# Sno_Shoe.net
KiCad netlist of a schematic drawn in EAGLE
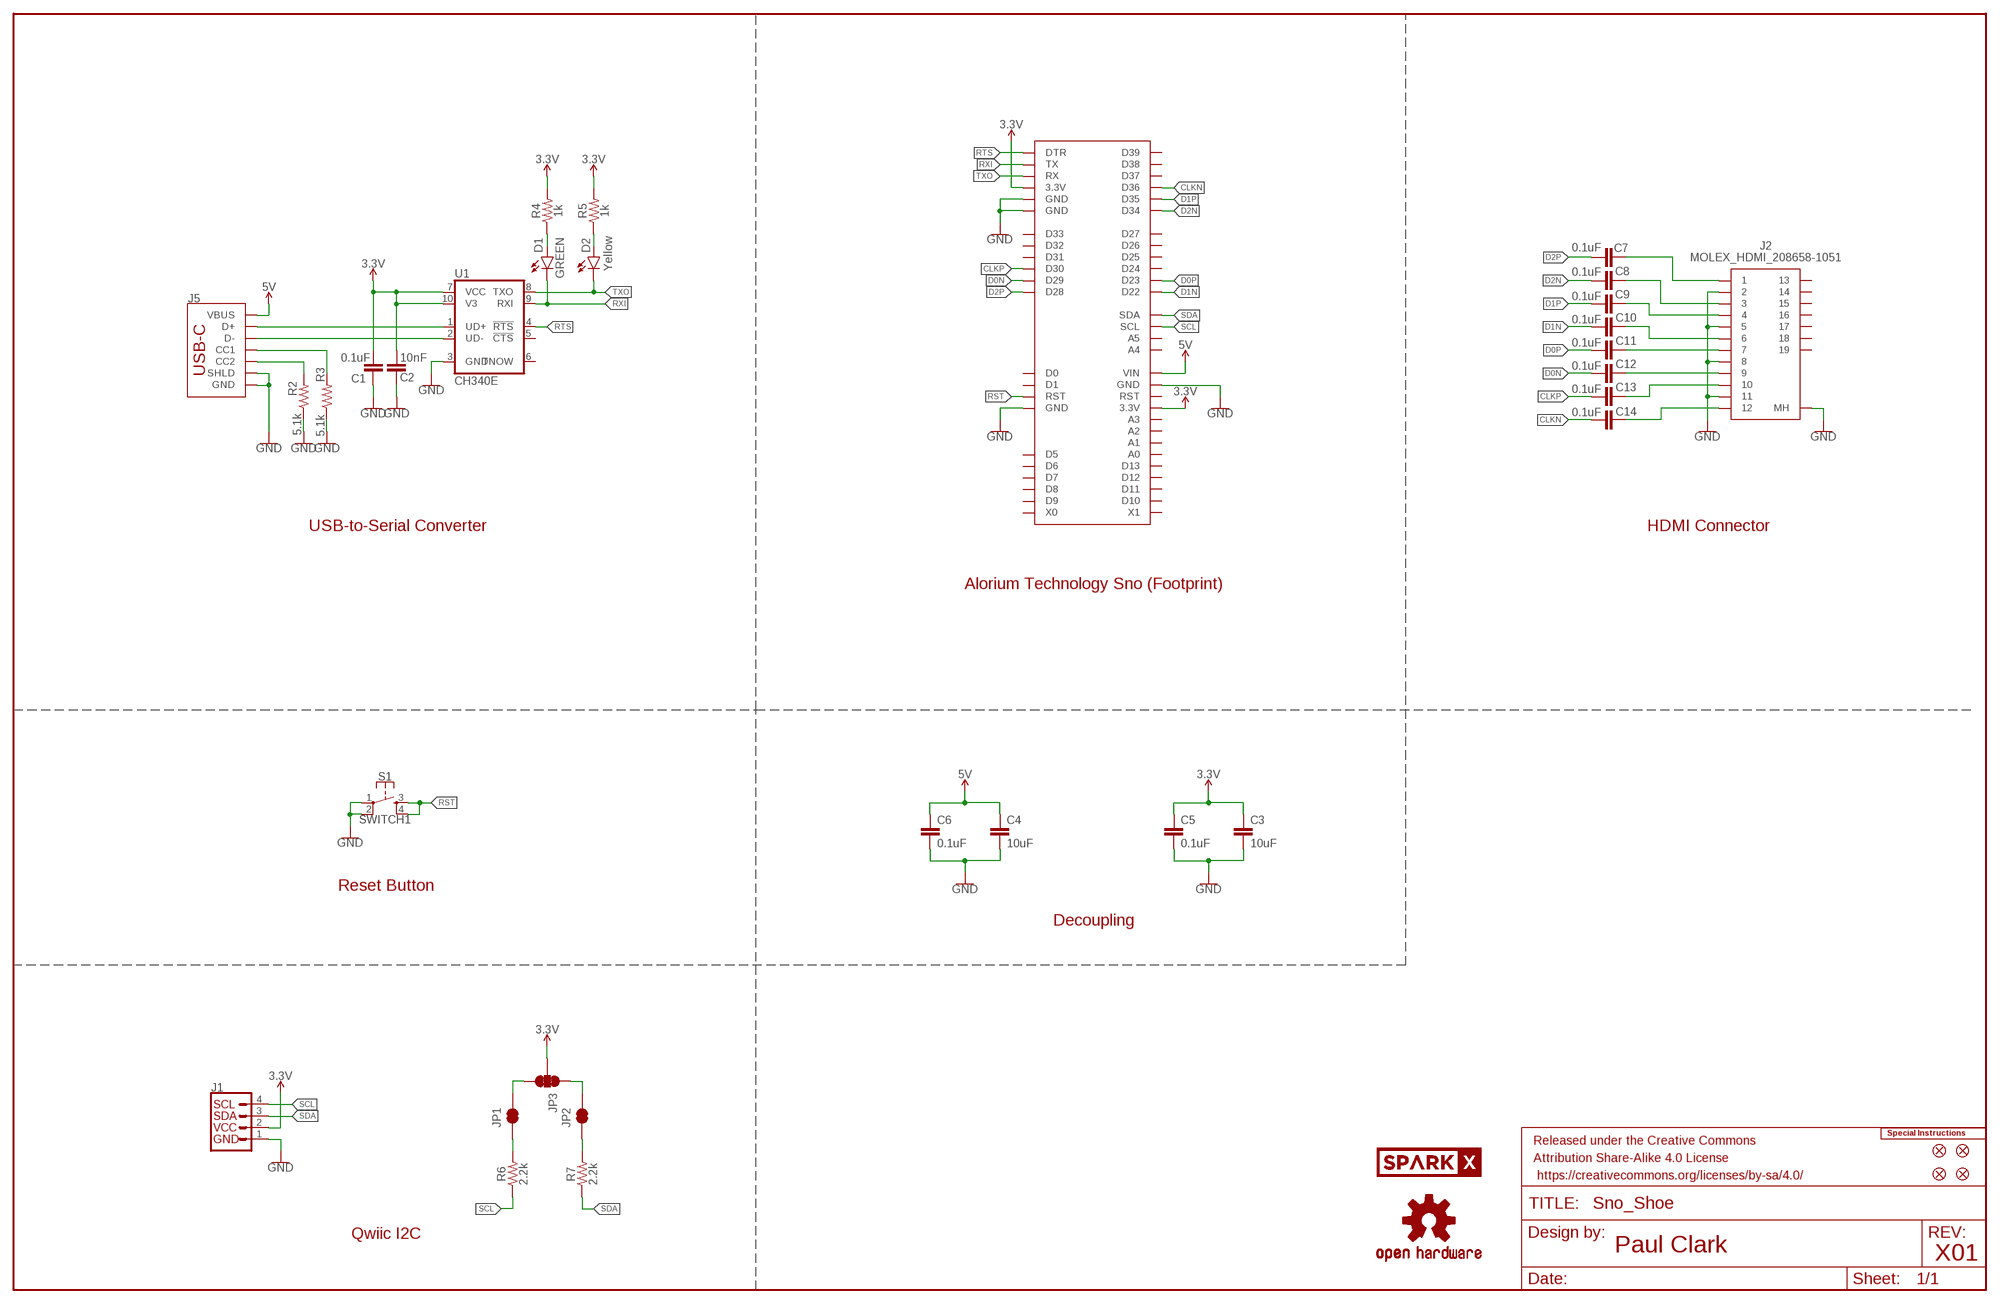
[diagram p0: schematic, sheet 1]

(export (version "E")
  (design (tool "Eeschema 10.0.6"))
  (components
    (comp (ref "C1")
      (value "0.1uF")
      (footprint "eagle-import:0402-TIGHT")
      (libsource (lib "eagle-import") (part "0.1UF-0402T-16V-10%"))
    )
    (comp (ref "C2")
      (value "10nF")
      (footprint "eagle-import:0402-TIGHT")
      (libsource (lib "eagle-import") (part "10NF-0402T-25V-10%"))
    )
    (comp (ref "C3")
      (value "10uF")
      (footprint "eagle-import:0402-TIGHT")
      (libsource (lib "eagle-import") (part "10UF-0402T-6.3V-20%"))
    )
    (comp (ref "C4")
      (value "10uF")
      (footprint "eagle-import:0805")
      (libsource (lib "eagle-import") (part "10UF-0805-10V-10%"))
    )
    (comp (ref "C5")
      (value "0.1uF")
      (footprint "eagle-import:0402-TIGHT")
      (libsource (lib "eagle-import") (part "0.1UF-0402T-10V-10%-X7R"))
    )
    (comp (ref "C6")
      (value "0.1uF")
      (footprint "eagle-import:0402-TIGHT")
      (libsource (lib "eagle-import") (part "0.1UF-0402T-10V-10%-X7R"))
    )
    (comp (ref "C7")
      (value "0.1uF")
      (footprint "eagle-import:0402-TIGHT")
      (libsource (lib "eagle-import") (part "0.1UF-0402T-10V-10%-X7R"))
    )
    (comp (ref "C8")
      (value "0.1uF")
      (footprint "eagle-import:0402-TIGHT")
      (libsource (lib "eagle-import") (part "0.1UF-0402T-10V-10%-X7R"))
    )
    (comp (ref "C9")
      (value "0.1uF")
      (footprint "eagle-import:0402-TIGHT")
      (libsource (lib "eagle-import") (part "0.1UF-0402T-10V-10%-X7R"))
    )
    (comp (ref "C10")
      (value "0.1uF")
      (footprint "eagle-import:0402-TIGHT")
      (libsource (lib "eagle-import") (part "0.1UF-0402T-10V-10%-X7R"))
    )
    (comp (ref "C11")
      (value "0.1uF")
      (footprint "eagle-import:0402-TIGHT")
      (libsource (lib "eagle-import") (part "0.1UF-0402T-10V-10%-X7R"))
    )
    (comp (ref "C12")
      (value "0.1uF")
      (footprint "eagle-import:0402-TIGHT")
      (libsource (lib "eagle-import") (part "0.1UF-0402T-10V-10%-X7R"))
    )
    (comp (ref "C13")
      (value "0.1uF")
      (footprint "eagle-import:0402-TIGHT")
      (libsource (lib "eagle-import") (part "0.1UF-0402T-10V-10%-X7R"))
    )
    (comp (ref "C14")
      (value "0.1uF")
      (footprint "eagle-import:0402-TIGHT")
      (libsource (lib "eagle-import") (part "0.1UF-0402T-10V-10%-X7R"))
    )
    (comp (ref "D1")
      (value "GREEN")
      (footprint "eagle-import:LED-0603")
      (libsource (lib "eagle-import") (part "LED-GREEN0603"))
    )
    (comp (ref "D2")
      (value "Yellow")
      (footprint "eagle-import:LED-0603")
      (libsource (lib "eagle-import") (part "LED-YELLOW0603"))
    )
    (comp (ref "FD1")
      (value "FIDUCIAL1X2")
      (footprint "eagle-import:FIDUCIAL-1X2")
      (libsource (lib "eagle-import") (part "FIDUCIAL1X2"))
    )
    (comp (ref "FD2")
      (value "FIDUCIAL1X2")
      (footprint "eagle-import:FIDUCIAL-1X2")
      (libsource (lib "eagle-import") (part "FIDUCIAL1X2"))
    )
    (comp (ref "FD3")
      (value "FIDUCIAL1X2")
      (footprint "eagle-import:FIDUCIAL-1X2")
      (libsource (lib "eagle-import") (part "FIDUCIAL1X2"))
    )
    (comp (ref "FD4")
      (value "FIDUCIAL1X2")
      (footprint "eagle-import:FIDUCIAL-1X2")
      (libsource (lib "eagle-import") (part "FIDUCIAL1X2"))
    )
    (comp (ref "FRAME1")
      (value "FRAME-LEDGER")
      (footprint "eagle-import:CREATIVE_COMMONS")
      (libsource (lib "eagle-import") (part "FRAME-LEDGER"))
    )
    (comp (ref "J1")
      (value "QWIIC_RIGHT_ANGLE")
      (footprint "eagle-import:JST04_1MM_RA")
      (libsource (lib "eagle-import") (part "QWIIC_CONNECTORJS-1MM"))
    )
    (comp (ref "J2")
      (value "MOLEX_HDMI_208658-1051")
      (footprint "eagle-import:MOLEX_HDMI_208658-1051")
      (fields
        (field (name "MANUFACTURER_PART_NUMBER") "208658-1051")
        (field (name "MOUSER_PART_NUMBER") "538-208658-1051")
      )
      (libsource (lib "eagle-import") (part "MOLEX_HDMI_208658-1051"))
    )
    (comp (ref "J5")
      (value "USB_C_4-LAYER_PADS")
      (footprint "eagle-import:USB-C-16P_4LAYER-PADS")
      (libsource (lib "eagle-import") (part "USB_C_4-LAYER_PADS"))
    )
    (comp (ref "JP1")
      (value "JUMPER-SMT_2_NC_TRACE_SILK")
      (footprint "eagle-import:SMT-JUMPER_2_NC_TRACE_SILK")
      (libsource (lib "eagle-import") (part "JUMPER-SMT_2_NC_TRACE_SILK"))
    )
    (comp (ref "JP2")
      (value "JUMPER-SMT_2_NC_TRACE_SILK")
      (footprint "eagle-import:SMT-JUMPER_2_NC_TRACE_SILK")
      (libsource (lib "eagle-import") (part "JUMPER-SMT_2_NC_TRACE_SILK"))
    )
    (comp (ref "JP3")
      (value "JUMPER-SMT_3_2-NC_TRACE_SILK")
      (footprint "eagle-import:SMT-JUMPER_3_2-NC_TRACE_SILK")
      (libsource (lib "eagle-import") (part "JUMPER-SMT_3_2-NC_TRACE_SILK"))
    )
    (comp (ref "LOGO1")
      (value "SPECIAL_INSTRUCTIONS-ORDERING")
      (footprint "eagle-import:ORDERING_INSTRUCTIONS")
      (libsource (lib "eagle-import") (part "SPECIAL_INSTRUCTIONS-ORDERING"))
    )
    (comp (ref "LOGO2")
      (value "OSHW-LOGOMINI")
      (footprint "eagle-import:OSHW-LOGO-MINI")
      (libsource (lib "eagle-import") (part "OSHW-LOGOMINI"))
    )
    (comp (ref "R2")
      (value "5.1k")
      (footprint "eagle-import:0402-TIGHT")
      (libsource (lib "eagle-import") (part "5.1KOHM-0402T-1/16W-1%"))
    )
    (comp (ref "R3")
      (value "5.1k")
      (footprint "eagle-import:0402-TIGHT")
      (libsource (lib "eagle-import") (part "5.1KOHM-0402T-1/16W-1%"))
    )
    (comp (ref "R4")
      (value "1k")
      (footprint "eagle-import:0402-TIGHT")
      (libsource (lib "eagle-import") (part "1KOHM-0402T-1/16W-1%"))
    )
    (comp (ref "R5")
      (value "1k")
      (footprint "eagle-import:0402-TIGHT")
      (libsource (lib "eagle-import") (part "1KOHM-0402T-1/16W-1%"))
    )
    (comp (ref "R6")
      (value "2.2k")
      (footprint "eagle-import:0402-TIGHT")
      (libsource (lib "eagle-import") (part "2.2KOHM-0402T-1/16W-1%"))
    )
    (comp (ref "R7")
      (value "2.2k")
      (footprint "eagle-import:0402-TIGHT")
      (libsource (lib "eagle-import") (part "2.2KOHM-0402T-1/16W-1%"))
    )
    (comp (ref "S1")
      (value "SWITCH1")
      (footprint "eagle-import:TACTILE_SWITCH_SMD_5.2MM")
      (libsource (lib "eagle-import") (part "MOMENTARY-SWITCH-SPST-2-SMD-5.2MM-TALL"))
    )
    (comp (ref "SPARKX2")
      (value "SPARKX-LOGO4")
      (footprint "eagle-import:SPARKX-MEDIUM")
      (libsource (lib "eagle-import") (part "SPARKX-LOGO4"))
    )
    (comp (ref "U$1")
      (value "SNO_MISSING_PINS")
      (footprint "eagle-import:SNO_MISSING_PINS")
      (libsource (lib "eagle-import") (part "SNO_MISSING_PINS"))
    )
    (comp (ref "U1")
      (value "CH340E")
      (footprint "eagle-import:MSOP10")
      (libsource (lib "eagle-import") (part "CH340E_MSOP10"))
    )
  )
  (nets
    (net (code "1") (name "3.3V") (class "Default")
      (node (ref "C1") (pin "1") (pinfunction "1_1") (pintype "passive"))
      (node (ref "C2") (pin "1") (pinfunction "1_1") (pintype "passive"))
      (node (ref "C3") (pin "1") (pinfunction "1_1") (pintype "passive"))
      (node (ref "C5") (pin "1") (pinfunction "1_1") (pintype "passive"))
      (node (ref "J1") (pin "2") (pinfunction "2_2") (pintype "power_in"))
      (node (ref "JP3") (pin "2") (pinfunction "2_2") (pintype "passive"))
      (node (ref "R4") (pin "2") (pinfunction "2_2") (pintype "passive"))
      (node (ref "R5") (pin "2") (pinfunction "2_2") (pintype "passive"))
      (node (ref "U$1") (pin "P$28") (pinfunction "3.3V_P$28") (pintype "bidirectional"))
      (node (ref "U$1") (pin "P$56") (pinfunction "3.3V_P$56") (pintype "power_in"))
      (node (ref "U1") (pin "10") (pinfunction "V3_10") (pintype "bidirectional"))
      (node (ref "U1") (pin "7") (pinfunction "VCC_7") (pintype "bidirectional"))
    )
    (net (code "2") (name "5V") (class "Default")
      (node (ref "C4") (pin "1") (pinfunction "1_1") (pintype "passive"))
      (node (ref "C6") (pin "1") (pinfunction "1_1") (pintype "passive"))
      (node (ref "J5") (pin "VBUS1") (pinfunction "VBUS_VBUS1") (pintype "bidirectional"))
      (node (ref "J5") (pin "VBUS2") (pinfunction "VBUS_VBUS2") (pintype "bidirectional"))
      (node (ref "U$1") (pin "P$31") (pinfunction "VIN_P$31") (pintype "power_in"))
    )
    (net (code "3") (name "CLKN") (class "Default")
      (node (ref "C14") (pin "1") (pinfunction "1_1") (pintype "passive"))
      (node (ref "U$1") (pin "P$50") (pinfunction "D36_P$50") (pintype "bidirectional"))
    )
    (net (code "4") (name "CLKP") (class "Default")
      (node (ref "C13") (pin "1") (pinfunction "1_1") (pintype "passive"))
      (node (ref "U$1") (pin "P$44") (pinfunction "D30_P$44") (pintype "bidirectional"))
    )
    (net (code "5") (name "D0N") (class "Default")
      (node (ref "C12") (pin "1") (pinfunction "1_1") (pintype "passive"))
      (node (ref "U$1") (pin "P$43") (pinfunction "D29_P$43") (pintype "bidirectional"))
    )
    (net (code "6") (name "D0P") (class "Default")
      (node (ref "C11") (pin "1") (pinfunction "1_1") (pintype "passive"))
      (node (ref "U$1") (pin "P$37") (pinfunction "D23_P$37") (pintype "bidirectional"))
    )
    (net (code "7") (name "D1N") (class "Default")
      (node (ref "C10") (pin "1") (pinfunction "1_1") (pintype "passive"))
      (node (ref "U$1") (pin "P$36") (pinfunction "D22_P$36") (pintype "bidirectional"))
    )
    (net (code "8") (name "D1P") (class "Default")
      (node (ref "C9") (pin "1") (pinfunction "1_1") (pintype "passive"))
      (node (ref "U$1") (pin "P$49") (pinfunction "D35_P$49") (pintype "bidirectional"))
    )
    (net (code "9") (name "D2N") (class "Default")
      (node (ref "C8") (pin "1") (pinfunction "1_1") (pintype "passive"))
      (node (ref "U$1") (pin "P$48") (pinfunction "D34_P$48") (pintype "bidirectional"))
    )
    (net (code "10") (name "D2P") (class "Default")
      (node (ref "C7") (pin "1") (pinfunction "1_1") (pintype "passive"))
      (node (ref "U$1") (pin "P$42") (pinfunction "D28_P$42") (pintype "bidirectional"))
    )
    (net (code "11") (name "GND") (class "Default")
      (node (ref "C1") (pin "2") (pinfunction "2_2") (pintype "passive"))
      (node (ref "C2") (pin "2") (pinfunction "2_2") (pintype "passive"))
      (node (ref "C3") (pin "2") (pinfunction "2_2") (pintype "passive"))
      (node (ref "C4") (pin "2") (pinfunction "2_2") (pintype "passive"))
      (node (ref "C5") (pin "2") (pinfunction "2_2") (pintype "passive"))
      (node (ref "C6") (pin "2") (pinfunction "2_2") (pintype "passive"))
      (node (ref "J1") (pin "1") (pinfunction "1_1") (pintype "power_in"))
      (node (ref "J2") (pin "11") (pinfunction "11_11") (pintype "bidirectional"))
      (node (ref "J2") (pin "2") (pinfunction "2_2") (pintype "bidirectional"))
      (node (ref "J2") (pin "5") (pinfunction "5_5") (pintype "bidirectional"))
      (node (ref "J2") (pin "8") (pinfunction "8_8") (pintype "bidirectional"))
      (node (ref "J2") (pin "MH1") (pinfunction "MH_MH1") (pintype "bidirectional"))
      (node (ref "J2") (pin "MH2") (pinfunction "MH_MH2") (pintype "bidirectional"))
      (node (ref "J2") (pin "MH3") (pinfunction "MH_MH3") (pintype "bidirectional"))
      (node (ref "J2") (pin "MH4") (pinfunction "MH_MH4") (pintype "bidirectional"))
      (node (ref "J5") (pin "GND") (pinfunction "GND_GND") (pintype "bidirectional"))
      (node (ref "J5") (pin "GND2") (pinfunction "GND_GND2") (pintype "bidirectional"))
      (node (ref "J5") (pin "SHLD1") (pinfunction "SHLD_SHLD1") (pintype "bidirectional"))
      (node (ref "J5") (pin "SHLD2") (pinfunction "SHLD_SHLD2") (pintype "bidirectional"))
      (node (ref "J5") (pin "SHLD3") (pinfunction "SHLD_SHLD3") (pintype "bidirectional"))
      (node (ref "J5") (pin "SHLD4") (pinfunction "SHLD_SHLD4") (pintype "bidirectional"))
      (node (ref "R2") (pin "1") (pinfunction "1_1") (pintype "passive"))
      (node (ref "R3") (pin "1") (pinfunction "1_1") (pintype "passive"))
      (node (ref "S1") (pin "1") (pinfunction "1_1") (pintype "passive"))
      (node (ref "S1") (pin "2") (pinfunction "2_2") (pintype "passive"))
      (node (ref "U$1") (pin "P$30") (pinfunction "GND_P$30") (pintype "power_in"))
      (node (ref "U$1") (pin "P$4") (pinfunction "GND_P$4") (pintype "bidirectional"))
      (node (ref "U$1") (pin "P$54") (pinfunction "GND_P$54") (pintype "power_in"))
      (node (ref "U$1") (pin "P$55") (pinfunction "GND_P$55") (pintype "power_in"))
      (node (ref "U1") (pin "3") (pinfunction "GND_3") (pintype "bidirectional"))
    )
    (net (code "12") (name "Net-(C7-Pad2)") (class "Default")
      (node (ref "C7") (pin "2") (pinfunction "2_2") (pintype "passive"))
      (node (ref "J2") (pin "1") (pinfunction "1_1") (pintype "bidirectional"))
    )
    (net (code "13") (name "Net-(C8-Pad2)") (class "Default")
      (node (ref "C8") (pin "2") (pinfunction "2_2") (pintype "passive"))
      (node (ref "J2") (pin "3") (pinfunction "3_3") (pintype "bidirectional"))
    )
    (net (code "14") (name "Net-(C9-Pad2)") (class "Default")
      (node (ref "C9") (pin "2") (pinfunction "2_2") (pintype "passive"))
      (node (ref "J2") (pin "4") (pinfunction "4_4") (pintype "bidirectional"))
    )
    (net (code "15") (name "Net-(C10-Pad2)") (class "Default")
      (node (ref "C10") (pin "2") (pinfunction "2_2") (pintype "passive"))
      (node (ref "J2") (pin "6") (pinfunction "6_6") (pintype "bidirectional"))
    )
    (net (code "16") (name "Net-(C11-Pad2)") (class "Default")
      (node (ref "C11") (pin "2") (pinfunction "2_2") (pintype "passive"))
      (node (ref "J2") (pin "7") (pinfunction "7_7") (pintype "bidirectional"))
    )
    (net (code "17") (name "Net-(C12-Pad2)") (class "Default")
      (node (ref "C12") (pin "2") (pinfunction "2_2") (pintype "passive"))
      (node (ref "J2") (pin "9") (pinfunction "9_9") (pintype "bidirectional"))
    )
    (net (code "18") (name "Net-(C13-Pad2)") (class "Default")
      (node (ref "C13") (pin "2") (pinfunction "2_2") (pintype "passive"))
      (node (ref "J2") (pin "10") (pinfunction "10_10") (pintype "bidirectional"))
    )
    (net (code "19") (name "Net-(C14-Pad2)") (class "Default")
      (node (ref "C14") (pin "2") (pinfunction "2_2") (pintype "passive"))
      (node (ref "J2") (pin "12") (pinfunction "12_12") (pintype "bidirectional"))
    )
    (net (code "20") (name "Net-(D1-PadA)") (class "Default")
      (node (ref "D1") (pin "A") (pinfunction "A_A") (pintype "passive"))
      (node (ref "R4") (pin "1") (pinfunction "1_1") (pintype "passive"))
    )
    (net (code "21") (name "Net-(D2-PadA)") (class "Default")
      (node (ref "D2") (pin "A") (pinfunction "A_A") (pintype "passive"))
      (node (ref "R5") (pin "1") (pinfunction "1_1") (pintype "passive"))
    )
    (net (code "22") (name "Net-(J5-CC1)") (class "Default")
      (node (ref "J5") (pin "A5") (pinfunction "CC1_A5") (pintype "bidirectional"))
      (node (ref "R3") (pin "2") (pinfunction "2_2") (pintype "passive"))
    )
    (net (code "23") (name "Net-(J5-CC2)") (class "Default")
      (node (ref "J5") (pin "B5") (pinfunction "CC2_B5") (pintype "bidirectional"))
      (node (ref "R2") (pin "2") (pinfunction "2_2") (pintype "passive"))
    )
    (net (code "24") (name "Net-(JP1-Pad1)") (class "Default")
      (node (ref "JP1") (pin "1") (pinfunction "1_1") (pintype "passive"))
      (node (ref "R6") (pin "2") (pinfunction "2_2") (pintype "passive"))
    )
    (net (code "25") (name "Net-(JP1-Pad2)") (class "Default")
      (node (ref "JP1") (pin "2") (pinfunction "2_2") (pintype "passive"))
      (node (ref "JP3") (pin "3") (pinfunction "3_3") (pintype "passive"))
    )
    (net (code "26") (name "Net-(JP2-Pad1)") (class "Default")
      (node (ref "JP2") (pin "1") (pinfunction "1_1") (pintype "passive"))
      (node (ref "R7") (pin "2") (pinfunction "2_2") (pintype "passive"))
    )
    (net (code "27") (name "Net-(JP2-Pad2)") (class "Default")
      (node (ref "JP2") (pin "2") (pinfunction "2_2") (pintype "passive"))
      (node (ref "JP3") (pin "1") (pinfunction "1_1") (pintype "passive"))
    )
    (net (code "28") (name "Net-(U1-UD+)") (class "Default")
      (node (ref "J5") (pin "A6") (pinfunction "D+_A6") (pintype "bidirectional"))
      (node (ref "J5") (pin "B6") (pinfunction "D+_B6") (pintype "bidirectional"))
      (node (ref "U1") (pin "1") (pinfunction "UD+_1") (pintype "bidirectional"))
    )
    (net (code "29") (name "Net-(U1-UD-)") (class "Default")
      (node (ref "J5") (pin "A7") (pinfunction "D-_A7") (pintype "bidirectional"))
      (node (ref "J5") (pin "B7") (pinfunction "D-_B7") (pintype "bidirectional"))
      (node (ref "U1") (pin "2") (pinfunction "UD-_2") (pintype "bidirectional"))
    )
    (net (code "30") (name "RST") (class "Default")
      (node (ref "S1") (pin "3") (pinfunction "3_3") (pintype "passive"))
      (node (ref "S1") (pin "4") (pinfunction "4_4") (pintype "passive"))
      (node (ref "U$1") (pin "P$3") (pinfunction "RST_P$3") (pintype "input"))
    )
    (net (code "31") (name "RTS") (class "Default")
      (node (ref "U$1") (pin "P$59") (pinfunction "DTR_P$59") (pintype "bidirectional"))
      (node (ref "U1") (pin "4") (pinfunction "~{RTS}_4") (pintype "bidirectional"))
    )
    (net (code "32") (name "RXI") (class "Default")
      (node (ref "D1") (pin "C") (pinfunction "C_C") (pintype "passive"))
      (node (ref "U$1") (pin "P$58") (pinfunction "TX_P$58") (pintype "bidirectional"))
      (node (ref "U1") (pin "9") (pinfunction "RXI_9") (pintype "bidirectional"))
    )
    (net (code "33") (name "SCL") (class "Default")
      (node (ref "J1") (pin "4") (pinfunction "4_4") (pintype "passive"))
      (node (ref "R6") (pin "1") (pinfunction "1_1") (pintype "passive"))
      (node (ref "U$1") (pin "P$34") (pinfunction "SCL_P$34") (pintype "bidirectional"))
    )
    (net (code "34") (name "SDA") (class "Default")
      (node (ref "J1") (pin "3") (pinfunction "3_3") (pintype "passive"))
      (node (ref "R7") (pin "1") (pinfunction "1_1") (pintype "passive"))
      (node (ref "U$1") (pin "P$35") (pinfunction "SDA_P$35") (pintype "bidirectional"))
    )
    (net (code "35") (name "TXO") (class "Default")
      (node (ref "D2") (pin "C") (pinfunction "C_C") (pintype "passive"))
      (node (ref "U$1") (pin "P$57") (pinfunction "RX_P$57") (pintype "bidirectional"))
      (node (ref "U1") (pin "8") (pinfunction "TXO_8") (pintype "bidirectional"))
    )
    (net (code "36") (name "unconnected-(J2-Pad13)") (class "Default")
      (node (ref "J2") (pin "13") (pinfunction "13_13") (pintype "bidirectional"))
    )
    (net (code "37") (name "unconnected-(J2-Pad14)") (class "Default")
      (node (ref "J2") (pin "14") (pinfunction "14_14") (pintype "bidirectional"))
    )
    (net (code "38") (name "unconnected-(J2-Pad15)") (class "Default")
      (node (ref "J2") (pin "15") (pinfunction "15_15") (pintype "bidirectional"))
    )
    (net (code "39") (name "unconnected-(J2-Pad16)") (class "Default")
      (node (ref "J2") (pin "16") (pinfunction "16_16") (pintype "bidirectional"))
    )
    (net (code "40") (name "unconnected-(J2-Pad17)") (class "Default")
      (node (ref "J2") (pin "17") (pinfunction "17_17") (pintype "bidirectional"))
    )
    (net (code "41") (name "unconnected-(J2-Pad18)") (class "Default")
      (node (ref "J2") (pin "18") (pinfunction "18_18") (pintype "bidirectional"))
    )
    (net (code "42") (name "unconnected-(J2-Pad19)") (class "Default")
      (node (ref "J2") (pin "19") (pinfunction "19_19") (pintype "bidirectional"))
    )
    (net (code "43") (name "unconnected-(U$1-A0-PadP$24)") (class "Default")
      (node (ref "U$1") (pin "P$24") (pinfunction "A0_P$24") (pintype "bidirectional"))
    )
    (net (code "44") (name "unconnected-(U$1-A1-PadP$25)") (class "Default")
      (node (ref "U$1") (pin "P$25") (pinfunction "A1_P$25") (pintype "bidirectional"))
    )
    (net (code "45") (name "unconnected-(U$1-A2-PadP$26)") (class "Default")
      (node (ref "U$1") (pin "P$26") (pinfunction "A2_P$26") (pintype "bidirectional"))
    )
    (net (code "46") (name "unconnected-(U$1-A3-PadP$27)") (class "Default")
      (node (ref "U$1") (pin "P$27") (pinfunction "A3_P$27") (pintype "bidirectional"))
    )
    (net (code "47") (name "unconnected-(U$1-A4-PadP$32)") (class "Default")
      (node (ref "U$1") (pin "P$32") (pinfunction "A4_P$32") (pintype "bidirectional"))
    )
    (net (code "48") (name "unconnected-(U$1-A5-PadP$33)") (class "Default")
      (node (ref "U$1") (pin "P$33") (pinfunction "A5_P$33") (pintype "bidirectional"))
    )
    (net (code "49") (name "unconnected-(U$1-D0-PadP$1)") (class "Default")
      (node (ref "U$1") (pin "P$1") (pinfunction "D0_P$1") (pintype "bidirectional"))
    )
    (net (code "50") (name "unconnected-(U$1-D1-PadP$2)") (class "Default")
      (node (ref "U$1") (pin "P$2") (pinfunction "D1_P$2") (pintype "bidirectional"))
    )
    (net (code "51") (name "unconnected-(U$1-D5-PadP$8)") (class "Default")
      (node (ref "U$1") (pin "P$8") (pinfunction "D5_P$8") (pintype "bidirectional"))
    )
    (net (code "52") (name "unconnected-(U$1-D6-PadP$9)") (class "Default")
      (node (ref "U$1") (pin "P$9") (pinfunction "D6_P$9") (pintype "bidirectional"))
    )
    (net (code "53") (name "unconnected-(U$1-D7-PadP$10)") (class "Default")
      (node (ref "U$1") (pin "P$10") (pinfunction "D7_P$10") (pintype "bidirectional"))
    )
    (net (code "54") (name "unconnected-(U$1-D8-PadP$11)") (class "Default")
      (node (ref "U$1") (pin "P$11") (pinfunction "D8_P$11") (pintype "bidirectional"))
    )
    (net (code "55") (name "unconnected-(U$1-D9-PadP$12)") (class "Default")
      (node (ref "U$1") (pin "P$12") (pinfunction "D9_P$12") (pintype "bidirectional"))
    )
    (net (code "56") (name "unconnected-(U$1-D10-PadP$20)") (class "Default")
      (node (ref "U$1") (pin "P$20") (pinfunction "D10_P$20") (pintype "bidirectional"))
    )
    (net (code "57") (name "unconnected-(U$1-D11-PadP$21)") (class "Default")
      (node (ref "U$1") (pin "P$21") (pinfunction "D11_P$21") (pintype "bidirectional"))
    )
    (net (code "58") (name "unconnected-(U$1-D12-PadP$22)") (class "Default")
      (node (ref "U$1") (pin "P$22") (pinfunction "D12_P$22") (pintype "bidirectional"))
    )
    (net (code "59") (name "unconnected-(U$1-D13-PadP$23)") (class "Default")
      (node (ref "U$1") (pin "P$23") (pinfunction "D13_P$23") (pintype "bidirectional"))
    )
    (net (code "60") (name "unconnected-(U$1-D24-PadP$38)") (class "Default")
      (node (ref "U$1") (pin "P$38") (pinfunction "D24_P$38") (pintype "bidirectional"))
    )
    (net (code "61") (name "unconnected-(U$1-D25-PadP$39)") (class "Default")
      (node (ref "U$1") (pin "P$39") (pinfunction "D25_P$39") (pintype "bidirectional"))
    )
    (net (code "62") (name "unconnected-(U$1-D26-PadP$40)") (class "Default")
      (node (ref "U$1") (pin "P$40") (pinfunction "D26_P$40") (pintype "bidirectional"))
    )
    (net (code "63") (name "unconnected-(U$1-D27-PadP$41)") (class "Default")
      (node (ref "U$1") (pin "P$41") (pinfunction "D27_P$41") (pintype "bidirectional"))
    )
    (net (code "64") (name "unconnected-(U$1-D31-PadP$45)") (class "Default")
      (node (ref "U$1") (pin "P$45") (pinfunction "D31_P$45") (pintype "bidirectional"))
    )
    (net (code "65") (name "unconnected-(U$1-D32-PadP$46)") (class "Default")
      (node (ref "U$1") (pin "P$46") (pinfunction "D32_P$46") (pintype "bidirectional"))
    )
    (net (code "66") (name "unconnected-(U$1-D33-PadP$47)") (class "Default")
      (node (ref "U$1") (pin "P$47") (pinfunction "D33_P$47") (pintype "bidirectional"))
    )
    (net (code "67") (name "unconnected-(U$1-D37-PadP$51)") (class "Default")
      (node (ref "U$1") (pin "P$51") (pinfunction "D37_P$51") (pintype "bidirectional"))
    )
    (net (code "68") (name "unconnected-(U$1-D38-PadP$52)") (class "Default")
      (node (ref "U$1") (pin "P$52") (pinfunction "D38_P$52") (pintype "bidirectional"))
    )
    (net (code "69") (name "unconnected-(U$1-D39-PadP$53)") (class "Default")
      (node (ref "U$1") (pin "P$53") (pinfunction "D39_P$53") (pintype "bidirectional"))
    )
    (net (code "70") (name "unconnected-(U$1-RST-PadP$29)") (class "Default")
      (node (ref "U$1") (pin "P$29") (pinfunction "RST_P$29") (pintype "input"))
    )
    (net (code "71") (name "unconnected-(U$1-X0-PadP$13)") (class "Default")
      (node (ref "U$1") (pin "P$13") (pinfunction "X0_P$13") (pintype "bidirectional"))
    )
    (net (code "72") (name "unconnected-(U$1-X1-PadP$19)") (class "Default")
      (node (ref "U$1") (pin "P$19") (pinfunction "X1_P$19") (pintype "bidirectional"))
    )
    (net (code "73") (name "unconnected-(U1-TNOW-Pad6)") (class "Default")
      (node (ref "U1") (pin "6") (pinfunction "TNOW_6") (pintype "bidirectional"))
    )
    (net (code "74") (name "unconnected-(U1-~{CTS}-Pad5)") (class "Default")
      (node (ref "U1") (pin "5") (pinfunction "~{CTS}_5") (pintype "bidirectional"))
    )
  )
)
